# roboproj-2.net
KiCad netlist of a schematic drawn in EAGLE
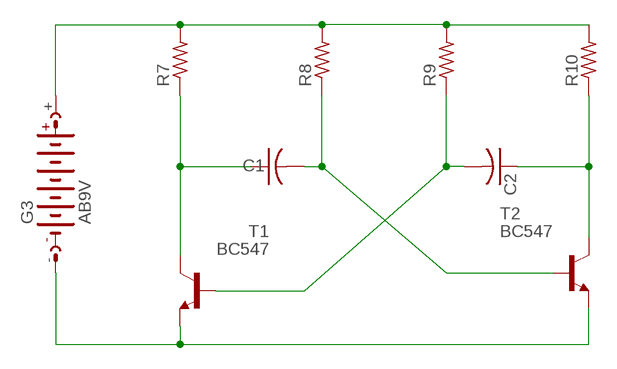
[diagram p0: schematic, sheet 1]
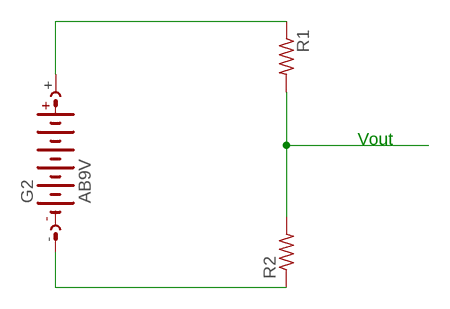
[diagram p1: schematic, sheet 2]
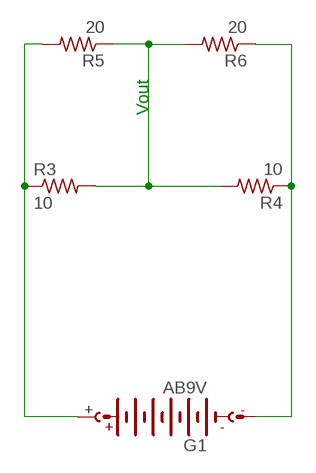
[diagram p2: schematic, sheet 3]
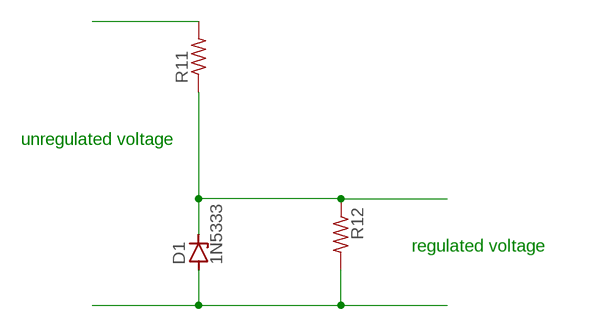
[diagram p3: schematic, sheet 4]

(export (version "E")
  (design (tool "Eeschema 10.0.6"))
  (components
    (comp (ref "D1")
      (value "1N5333")
      (footprint "eagle-import:C1702-15")
      (libsource (lib "eagle-import") (part "1N5333"))
    )
    (comp (ref "R11")
      (value "R-US_R0805")
      (footprint "eagle-import:R0805")
      (libsource (lib "eagle-import") (part "R-US_R0805"))
    )
    (comp (ref "R12")
      (value "R-US_R0805")
      (footprint "eagle-import:R0805")
      (libsource (lib "eagle-import") (part "R-US_R0805"))
    )
    (comp (ref "G1")
      (value "AB9V")
      (footprint "eagle-import:AB9V")
      (libsource (lib "eagle-import") (part "AB9V"))
    )
    (comp (ref "R3")
      (value "10")
      (footprint "eagle-import:R0805")
      (libsource (lib "eagle-import") (part "R-US_R0805"))
    )
    (comp (ref "R4")
      (value "10")
      (footprint "eagle-import:R0805")
      (libsource (lib "eagle-import") (part "R-US_R0805"))
    )
    (comp (ref "R5")
      (value "20")
      (footprint "eagle-import:R0805")
      (libsource (lib "eagle-import") (part "R-US_R0805"))
    )
    (comp (ref "R6")
      (value "20")
      (footprint "eagle-import:R0805")
      (libsource (lib "eagle-import") (part "R-US_R0805"))
    )
    (comp (ref "G2")
      (value "AB9V")
      (footprint "eagle-import:AB9V")
      (libsource (lib "eagle-import") (part "AB9V"))
    )
    (comp (ref "R1")
      (value "R-US_R0805")
      (footprint "eagle-import:R0805")
      (libsource (lib "eagle-import") (part "R-US_R0805"))
    )
    (comp (ref "R2")
      (value "R-US_R0805")
      (footprint "eagle-import:R0805")
      (libsource (lib "eagle-import") (part "R-US_R0805"))
    )
    (comp (ref "C1")
      (value "C-USC0805")
      (footprint "eagle-import:C0805")
      (libsource (lib "eagle-import") (part "C-USC0805"))
    )
    (comp (ref "C2")
      (value "C-USC0805")
      (footprint "eagle-import:C0805")
      (libsource (lib "eagle-import") (part "C-USC0805"))
    )
    (comp (ref "G3")
      (value "AB9V")
      (footprint "eagle-import:AB9V")
      (libsource (lib "eagle-import") (part "AB9V"))
    )
    (comp (ref "R7")
      (value "R-US_R0805")
      (footprint "eagle-import:R0805")
      (libsource (lib "eagle-import") (part "R-US_R0805"))
    )
    (comp (ref "R8")
      (value "R-US_R0805")
      (footprint "eagle-import:R0805")
      (libsource (lib "eagle-import") (part "R-US_R0805"))
    )
    (comp (ref "R9")
      (value "R-US_R0805")
      (footprint "eagle-import:R0805")
      (libsource (lib "eagle-import") (part "R-US_R0805"))
    )
    (comp (ref "R10")
      (value "R-US_R0805")
      (footprint "eagle-import:R0805")
      (libsource (lib "eagle-import") (part "R-US_R0805"))
    )
    (comp (ref "T1")
      (value "BC547")
      (footprint "eagle-import:TO92")
      (libsource (lib "eagle-import") (part "BC547"))
    )
    (comp (ref "T2")
      (value "BC547")
      (footprint "eagle-import:TO92")
      (libsource (lib "eagle-import") (part "BC547"))
    )
  )
  (nets
    (net (code "1") (name "Net-(D1-PadA)") (class "Default")
      (node (ref "D1") (pin "A") (pinfunction "A_A") (pintype "passive"))
      (node (ref "R12") (pin "2") (pinfunction "2_2") (pintype "passive"))
    )
    (net (code "2") (name "Net-(D1-PadC)") (class "Default")
      (node (ref "D1") (pin "C") (pinfunction "C_C") (pintype "passive"))
      (node (ref "R11") (pin "1") (pinfunction "1_1") (pintype "passive"))
      (node (ref "R12") (pin "1") (pinfunction "1_1") (pintype "passive"))
    )
    (net (code "3") (name "Net-(G1-Pad+)") (class "Default")
      (node (ref "G1") (pin "+") (pinfunction "+_+") (pintype "passive"))
      (node (ref "R3") (pin "1") (pinfunction "1_1") (pintype "passive"))
      (node (ref "R5") (pin "2") (pinfunction "2_2") (pintype "passive"))
    )
    (net (code "4") (name "Net-(G1-Pad-)") (class "Default")
      (node (ref "G1") (pin "-") (pinfunction "-_-") (pintype "passive"))
      (node (ref "R4") (pin "1") (pinfunction "1_1") (pintype "passive"))
      (node (ref "R6") (pin "1") (pinfunction "1_1") (pintype "passive"))
    )
    (net (code "5") (name "Net-(G2-Pad+)") (class "Default")
      (node (ref "G2") (pin "+") (pinfunction "+_+") (pintype "passive"))
      (node (ref "R1") (pin "1") (pinfunction "1_1") (pintype "passive"))
    )
    (net (code "6") (name "Net-(G2-Pad-)") (class "Default")
      (node (ref "G2") (pin "-") (pinfunction "-_-") (pintype "passive"))
      (node (ref "R2") (pin "1") (pinfunction "1_1") (pintype "passive"))
    )
    (net (code "7") (name "Net-(G3-Pad+)") (class "Default")
      (node (ref "G3") (pin "+") (pinfunction "+_+") (pintype "passive"))
      (node (ref "R10") (pin "2") (pinfunction "2_2") (pintype "passive"))
      (node (ref "R7") (pin "2") (pinfunction "2_2") (pintype "passive"))
      (node (ref "R8") (pin "2") (pinfunction "2_2") (pintype "passive"))
      (node (ref "R9") (pin "2") (pinfunction "2_2") (pintype "passive"))
    )
    (net (code "8") (name "Net-(R1-Pad2)") (class "Default")
      (node (ref "R1") (pin "2") (pinfunction "2_2") (pintype "passive"))
      (node (ref "R2") (pin "2") (pinfunction "2_2") (pintype "passive"))
    )
    (net (code "9") (name "Net-(R3-Pad2)") (class "Default")
      (node (ref "R3") (pin "2") (pinfunction "2_2") (pintype "passive"))
      (node (ref "R4") (pin "2") (pinfunction "2_2") (pintype "passive"))
      (node (ref "R5") (pin "1") (pinfunction "1_1") (pintype "passive"))
      (node (ref "R6") (pin "2") (pinfunction "2_2") (pintype "passive"))
    )
    (net (code "10") (name "Net-(T1-B)") (class "Default")
      (node (ref "C2") (pin "2") (pinfunction "2_2") (pintype "passive"))
      (node (ref "R9") (pin "1") (pinfunction "1_1") (pintype "passive"))
      (node (ref "T1") (pin "2") (pinfunction "B_2") (pintype "passive"))
    )
    (net (code "11") (name "Net-(T1-C)") (class "Default")
      (node (ref "C1") (pin "1") (pinfunction "1_1") (pintype "passive"))
      (node (ref "R7") (pin "1") (pinfunction "1_1") (pintype "passive"))
      (node (ref "T1") (pin "3") (pinfunction "C_3") (pintype "passive"))
    )
    (net (code "12") (name "Net-(T1-E)") (class "Default")
      (node (ref "G3") (pin "-") (pinfunction "-_-") (pintype "passive"))
      (node (ref "T1") (pin "1") (pinfunction "E_1") (pintype "passive"))
      (node (ref "T2") (pin "1") (pinfunction "E_1") (pintype "passive"))
    )
    (net (code "13") (name "Net-(T2-B)") (class "Default")
      (node (ref "C1") (pin "2") (pinfunction "2_2") (pintype "passive"))
      (node (ref "R8") (pin "1") (pinfunction "1_1") (pintype "passive"))
      (node (ref "T2") (pin "2") (pinfunction "B_2") (pintype "passive"))
    )
    (net (code "14") (name "Net-(T2-C)") (class "Default")
      (node (ref "C2") (pin "1") (pinfunction "1_1") (pintype "passive"))
      (node (ref "R10") (pin "1") (pinfunction "1_1") (pintype "passive"))
      (node (ref "T2") (pin "3") (pinfunction "C_3") (pintype "passive"))
    )
    (net (code "15") (name "unconnected-(R11-Pad2)") (class "Default")
      (node (ref "R11") (pin "2") (pinfunction "2_2") (pintype "passive"))
    )
  )
)
